# usb-shock-buzzer.net
KiCad netlist of a schematic drawn in EAGLE
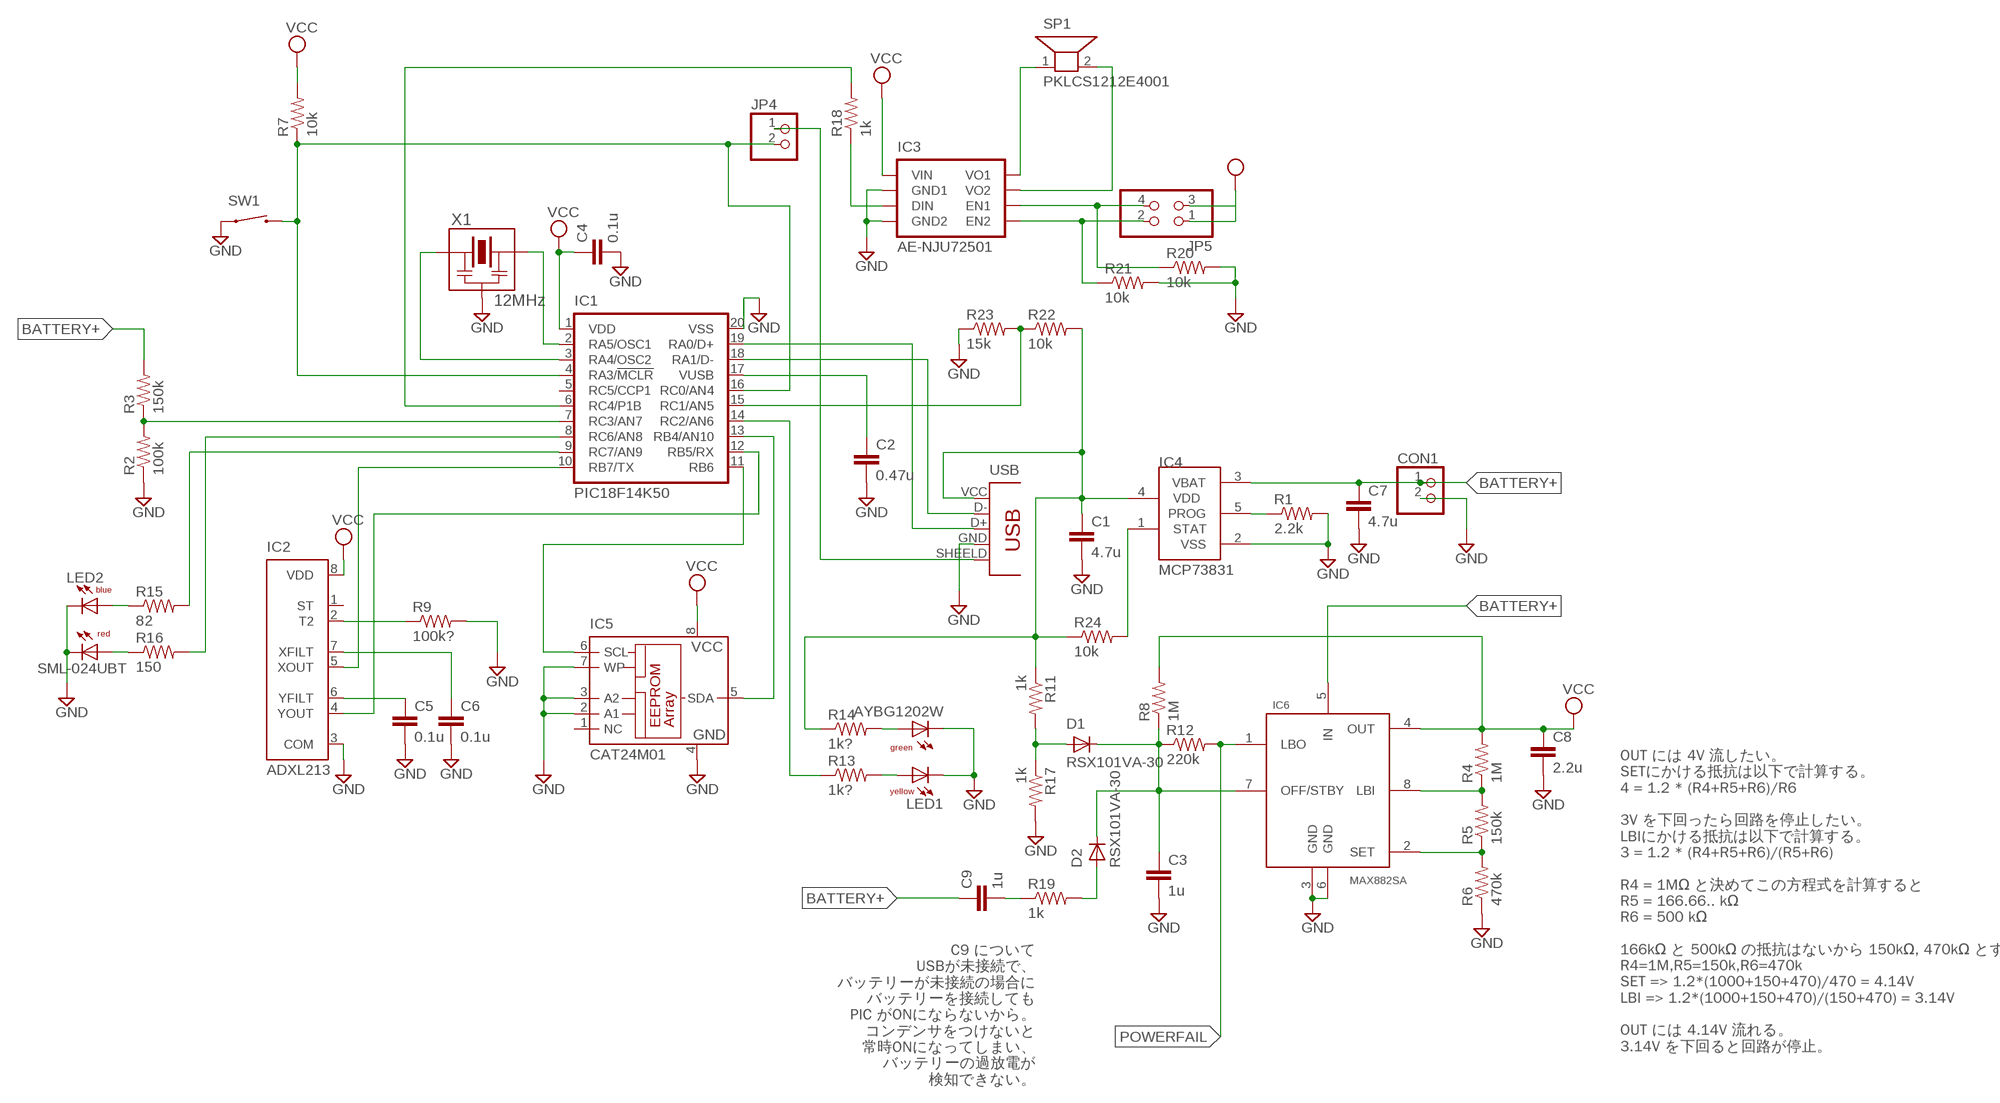
[diagram p0: schematic, sheet 1]

(export (version "E")
  (design (tool "Eeschema 10.0.6"))
  (components
    (comp (ref "C1")
      (value "4.7u")
      (footprint "eagle-import:C0805")
      (libsource (lib "eagle-import") (part "C-EUC0805"))
    )
    (comp (ref "C2")
      (value "0.47u")
      (footprint "eagle-import:C0805")
      (libsource (lib "eagle-import") (part "C-EUC0805"))
    )
    (comp (ref "C3")
      (value "1u")
      (footprint "eagle-import:C0805")
      (libsource (lib "eagle-import") (part "C-EUC0805"))
    )
    (comp (ref "C4")
      (value "0.1u")
      (footprint "eagle-import:C0805")
      (libsource (lib "eagle-import") (part "C-EUC0805"))
    )
    (comp (ref "C5")
      (value "0.1u")
      (footprint "eagle-import:C0805")
      (libsource (lib "eagle-import") (part "C-EUC0805"))
    )
    (comp (ref "C6")
      (value "0.1u")
      (footprint "eagle-import:C0805")
      (libsource (lib "eagle-import") (part "C-EUC0805"))
    )
    (comp (ref "C7")
      (value "4.7u")
      (footprint "eagle-import:C0805")
      (libsource (lib "eagle-import") (part "C-EUC0805"))
    )
    (comp (ref "C8")
      (value "2.2u")
      (footprint "eagle-import:C1206")
      (libsource (lib "eagle-import") (part "C-EUC1206"))
    )
    (comp (ref "C9")
      (value "1u")
      (footprint "eagle-import:C0805")
      (libsource (lib "eagle-import") (part "C-EUC0805"))
    )
    (comp (ref "CON1")
      (value "PH-2PIN")
      (footprint "eagle-import:PH-2PIN")
      (libsource (lib "eagle-import") (part "PH-2PIN"))
    )
    (comp (ref "D1")
      (value "RSX101VA-30")
      (footprint "eagle-import:RSX101VA")
      (libsource (lib "eagle-import") (part "RSX101VA-30"))
    )
    (comp (ref "D2")
      (value "RSX101VA-30")
      (footprint "eagle-import:RSX101VA")
      (libsource (lib "eagle-import") (part "RSX101VA-30"))
    )
    (comp (ref "IC1")
      (value "PIC18F14K50")
      (footprint "eagle-import:SO20")
      (libsource (lib "eagle-import") (part "PIC18F14K50"))
    )
    (comp (ref "IC2")
      (value "ADXL213")
      (footprint "eagle-import:LCC8")
      (libsource (lib "eagle-import") (part "ADXL213"))
    )
    (comp (ref "IC3")
      (value "AE-NJU72501")
      (footprint "eagle-import:AE-NJU72501")
      (libsource (lib "eagle-import") (part "AE-NJU72501"))
    )
    (comp (ref "IC4")
      (value "MCP73831")
      (footprint "eagle-import:SOT23-5L")
      (libsource (lib "eagle-import") (part "MCP73831"))
    )
    (comp (ref "IC5")
      (value "CAT24M01")
      (footprint "eagle-import:SOIC")
      (libsource (lib "eagle-import") (part "CAT24M01"))
    )
    (comp (ref "IC6")
      (value "MAX882SA")
      (footprint "eagle-import:8-SO")
      (libsource (lib "eagle-import") (part "MAX882SA"))
    )
    (comp (ref "JP4")
      (value "PINHD-1X2")
      (footprint "eagle-import:1X02")
      (libsource (lib "eagle-import") (part "PINHD-1X2"))
    )
    (comp (ref "JP5")
      (value "PINHD-2X2")
      (footprint "eagle-import:2X02")
      (libsource (lib "eagle-import") (part "PINHD-2X2"))
    )
    (comp (ref "LED1")
      (value "AYBG1202W")
      (footprint "eagle-import:AYBG1202W")
      (libsource (lib "eagle-import") (part "AYBG1202W"))
    )
    (comp (ref "LED2")
      (value "SML-024UBT")
      (footprint "eagle-import:SML-02")
      (libsource (lib "eagle-import") (part "2COLOR-BR"))
    )
    (comp (ref "R1")
      (value "2.2k")
      (footprint "eagle-import:M0805")
      (libsource (lib "eagle-import") (part "R-US_M0805"))
    )
    (comp (ref "R2")
      (value "100k")
      (footprint "eagle-import:M0805")
      (libsource (lib "eagle-import") (part "R-US_M0805"))
    )
    (comp (ref "R3")
      (value "150k")
      (footprint "eagle-import:M0805")
      (libsource (lib "eagle-import") (part "R-US_M0805"))
    )
    (comp (ref "R4")
      (value "1M")
      (footprint "eagle-import:R0805")
      (libsource (lib "eagle-import") (part "R-US_R0805"))
    )
    (comp (ref "R5")
      (value "150k")
      (footprint "eagle-import:M0805")
      (libsource (lib "eagle-import") (part "R-US_M0805"))
    )
    (comp (ref "R6")
      (value "470k")
      (footprint "eagle-import:M0805")
      (libsource (lib "eagle-import") (part "R-US_M0805"))
    )
    (comp (ref "R7")
      (value "10k")
      (footprint "eagle-import:M0805")
      (libsource (lib "eagle-import") (part "R-US_M0805"))
    )
    (comp (ref "R8")
      (value "1M")
      (footprint "eagle-import:M0805")
      (libsource (lib "eagle-import") (part "R-US_M0805"))
    )
    (comp (ref "R9")
      (value "100k?")
      (footprint "eagle-import:M0805")
      (libsource (lib "eagle-import") (part "R-US_M0805"))
    )
    (comp (ref "R11")
      (value "1k")
      (footprint "eagle-import:M0805")
      (libsource (lib "eagle-import") (part "R-US_M0805"))
    )
    (comp (ref "R12")
      (value "220k")
      (footprint "eagle-import:M0805")
      (libsource (lib "eagle-import") (part "R-US_M0805"))
    )
    (comp (ref "R13")
      (value "1k?")
      (footprint "eagle-import:M0805")
      (libsource (lib "eagle-import") (part "R-US_M0805"))
    )
    (comp (ref "R14")
      (value "1k?")
      (footprint "eagle-import:M0805")
      (libsource (lib "eagle-import") (part "R-US_M0805"))
    )
    (comp (ref "R15")
      (value "82")
      (footprint "eagle-import:M0805")
      (libsource (lib "eagle-import") (part "R-US_M0805"))
    )
    (comp (ref "R16")
      (value "150")
      (footprint "eagle-import:M0805")
      (libsource (lib "eagle-import") (part "R-US_M0805"))
    )
    (comp (ref "R17")
      (value "1k")
      (footprint "eagle-import:M0805")
      (libsource (lib "eagle-import") (part "R-US_M0805"))
    )
    (comp (ref "R18")
      (value "1k")
      (footprint "eagle-import:M0805")
      (libsource (lib "eagle-import") (part "R-US_M0805"))
    )
    (comp (ref "R19")
      (value "1k")
      (footprint "eagle-import:M0805")
      (libsource (lib "eagle-import") (part "R-US_M0805"))
    )
    (comp (ref "R20")
      (value "10k")
      (footprint "eagle-import:M0805")
      (libsource (lib "eagle-import") (part "R-US_M0805"))
    )
    (comp (ref "R21")
      (value "10k")
      (footprint "eagle-import:M0805")
      (libsource (lib "eagle-import") (part "R-US_M0805"))
    )
    (comp (ref "R22")
      (value "10k")
      (footprint "eagle-import:M0805")
      (libsource (lib "eagle-import") (part "R-US_M0805"))
    )
    (comp (ref "R23")
      (value "15k")
      (footprint "eagle-import:M0805")
      (libsource (lib "eagle-import") (part "R-US_M0805"))
    )
    (comp (ref "R24")
      (value "10k")
      (footprint "eagle-import:M0805")
      (libsource (lib "eagle-import") (part "R-US_M0805"))
    )
    (comp (ref "SP1")
      (value "PKLCS1212E4001")
      (footprint "eagle-import:PKLCS1212E4001")
      (libsource (lib "eagle-import") (part "PKLCS1212E4001"))
    )
    (comp (ref "SW1")
      (value "TVBP06")
      (footprint "eagle-import:TVBP06")
      (libsource (lib "eagle-import") (part "TVBP06"))
    )
    (comp (ref "USB")
      (value "TYPE-A+SHILED")
      (footprint "eagle-import:TYPE-A")
      (libsource (lib "eagle-import") (part "TYPE-A+SHILED"))
    )
    (comp (ref "X1")
      (value "12MHz")
      (footprint "eagle-import:CSTCE")
      (libsource (lib "eagle-import") (part "CSTCE12M0G15L"))
    )
  )
  (nets
    (net (code "1") (name "BATTERY+") (class "Default")
      (node (ref "C7") (pin "1") (pinfunction "1_1") (pintype "passive"))
      (node (ref "C9") (pin "1") (pinfunction "1_1") (pintype "passive"))
      (node (ref "CON1") (pin "1") (pinfunction "1_1") (pintype "passive"))
      (node (ref "IC4") (pin "3") (pinfunction "VBAT_3") (pintype "bidirectional"))
      (node (ref "IC6") (pin "5") (pinfunction "IN_5") (pintype "power_in"))
      (node (ref "R3") (pin "2") (pinfunction "2_2") (pintype "passive"))
    )
    (net (code "2") (name "GND") (class "Default")
      (node (ref "C1") (pin "2") (pinfunction "2_2") (pintype "passive"))
      (node (ref "C2") (pin "2") (pinfunction "2_2") (pintype "passive"))
      (node (ref "C3") (pin "2") (pinfunction "2_2") (pintype "passive"))
      (node (ref "C4") (pin "2") (pinfunction "2_2") (pintype "passive"))
      (node (ref "C5") (pin "2") (pinfunction "2_2") (pintype "passive"))
      (node (ref "C6") (pin "2") (pinfunction "2_2") (pintype "passive"))
      (node (ref "C7") (pin "2") (pinfunction "2_2") (pintype "passive"))
      (node (ref "C8") (pin "2") (pinfunction "2_2") (pintype "passive"))
      (node (ref "CON1") (pin "2") (pinfunction "2_2") (pintype "passive"))
      (node (ref "IC1") (pin "20") (pinfunction "VSS_20") (pintype "power_in"))
      (node (ref "IC2") (pin "3") (pinfunction "COM_3") (pintype "input"))
      (node (ref "IC3") (pin "2") (pinfunction "GND1_2") (pintype "power_in"))
      (node (ref "IC3") (pin "4") (pinfunction "GND2_4") (pintype "power_in"))
      (node (ref "IC4") (pin "2") (pinfunction "VSS_2") (pintype "bidirectional"))
      (node (ref "IC5") (pin "2") (pinfunction "A1_2") (pintype "input"))
      (node (ref "IC5") (pin "3") (pinfunction "A2_3") (pintype "input"))
      (node (ref "IC5") (pin "4") (pinfunction "GND_4") (pintype "power_in"))
      (node (ref "IC5") (pin "7") (pinfunction "WP_7") (pintype "input"))
      (node (ref "IC6") (pin "3") (pinfunction "GND_3") (pintype "power_in"))
      (node (ref "IC6") (pin "6") (pinfunction "GND_6") (pintype "power_in"))
      (node (ref "LED1") (pin "2") (pinfunction "CC1_2") (pintype "passive"))
      (node (ref "LED1") (pin "4") (pinfunction "CC2_4") (pintype "passive"))
      (node (ref "LED2") (pin "1") (pinfunction "CC1_1") (pintype "passive"))
      (node (ref "LED2") (pin "3") (pinfunction "CC2_3") (pintype "passive"))
      (node (ref "R1") (pin "2") (pinfunction "2_2") (pintype "passive"))
      (node (ref "R17") (pin "2") (pinfunction "2_2") (pintype "passive"))
      (node (ref "R2") (pin "1") (pinfunction "1_1") (pintype "passive"))
      (node (ref "R20") (pin "2") (pinfunction "2_2") (pintype "passive"))
      (node (ref "R21") (pin "2") (pinfunction "2_2") (pintype "passive"))
      (node (ref "R23") (pin "1") (pinfunction "1_1") (pintype "passive"))
      (node (ref "R6") (pin "1") (pinfunction "1_1") (pintype "passive"))
      (node (ref "R9") (pin "2") (pinfunction "2_2") (pintype "passive"))
      (node (ref "SW1") (pin "1") (pinfunction "1_1") (pintype "passive"))
      (node (ref "USB") (pin "GND") (pinfunction "4_GND") (pintype "power_in"))
      (node (ref "X1") (pin "2") (pinfunction "GND_2") (pintype "bidirectional"))
    )
    (net (code "3") (name "Net-(C9-Pad2)") (class "Default")
      (node (ref "C9") (pin "2") (pinfunction "2_2") (pintype "passive"))
      (node (ref "R19") (pin "1") (pinfunction "1_1") (pintype "passive"))
    )
    (net (code "4") (name "Net-(D1-A)") (class "Default")
      (node (ref "D1") (pin "ANODE") (pinfunction "A_ANODE") (pintype "passive"))
      (node (ref "R11") (pin "2") (pinfunction "2_2") (pintype "passive"))
      (node (ref "R17") (pin "1") (pinfunction "1_1") (pintype "passive"))
    )
    (net (code "5") (name "Net-(D1-C)") (class "Default")
      (node (ref "C3") (pin "1") (pinfunction "1_1") (pintype "passive"))
      (node (ref "D1") (pin "CATHODE") (pinfunction "C_CATHODE") (pintype "passive"))
      (node (ref "D2") (pin "CATHODE") (pinfunction "C_CATHODE") (pintype "passive"))
      (node (ref "IC6") (pin "7") (pinfunction "OFF/STBY_7") (pintype "passive"))
      (node (ref "R12") (pin "1") (pinfunction "1_1") (pintype "passive"))
      (node (ref "R8") (pin "1") (pinfunction "1_1") (pintype "passive"))
    )
    (net (code "6") (name "Net-(D2-A)") (class "Default")
      (node (ref "D2") (pin "ANODE") (pinfunction "A_ANODE") (pintype "passive"))
      (node (ref "R19") (pin "2") (pinfunction "2_2") (pintype "passive"))
    )
    (net (code "7") (name "Net-(IC1-RA0{slash}D+)") (class "Default")
      (node (ref "IC1") (pin "19") (pinfunction "RA0/D+_19") (pintype "bidirectional"))
      (node (ref "USB") (pin "D+") (pinfunction "3_D+") (pintype "passive"))
    )
    (net (code "8") (name "Net-(IC1-RA1{slash}D-)") (class "Default")
      (node (ref "IC1") (pin "18") (pinfunction "RA1/D-_18") (pintype "bidirectional"))
      (node (ref "USB") (pin "D-") (pinfunction "2_D-") (pintype "passive"))
    )
    (net (code "9") (name "Net-(IC1-RA3{slash}~{MCLR})") (class "Default")
      (node (ref "IC1") (pin "16") (pinfunction "RC0/AN4_16") (pintype "bidirectional"))
      (node (ref "IC1") (pin "4") (pinfunction "RA3/~{MCLR}_4") (pintype "bidirectional"))
      (node (ref "JP4") (pin "2") (pinfunction "2_2") (pintype "passive"))
      (node (ref "R7") (pin "1") (pinfunction "1_1") (pintype "passive"))
      (node (ref "SW1") (pin "2") (pinfunction "2_2") (pintype "passive"))
    )
    (net (code "10") (name "Net-(IC1-RA4{slash}OSC2)") (class "Default")
      (node (ref "IC1") (pin "3") (pinfunction "RA4/OSC2_3") (pintype "bidirectional"))
      (node (ref "X1") (pin "1") (pinfunction "LFT_1") (pintype "bidirectional"))
    )
    (net (code "11") (name "Net-(IC1-RA5{slash}OSC1)") (class "Default")
      (node (ref "IC1") (pin "2") (pinfunction "RA5/OSC1_2") (pintype "bidirectional"))
      (node (ref "X1") (pin "3") (pinfunction "RIT_3") (pintype "bidirectional"))
    )
    (net (code "12") (name "Net-(IC1-RB4{slash}AN10)") (class "Default")
      (node (ref "IC1") (pin "13") (pinfunction "RB4/AN10_13") (pintype "bidirectional"))
      (node (ref "IC5") (pin "5") (pinfunction "SDA_5") (pintype "bidirectional"))
    )
    (net (code "13") (name "Net-(IC1-RB5{slash}RX)") (class "Default")
      (node (ref "IC1") (pin "12") (pinfunction "RB5/RX_12") (pintype "bidirectional"))
      (node (ref "IC2") (pin "4") (pinfunction "YOUT_4") (pintype "input"))
    )
    (net (code "14") (name "Net-(IC1-RB6)") (class "Default")
      (node (ref "IC1") (pin "11") (pinfunction "RB6_11") (pintype "bidirectional"))
      (node (ref "IC5") (pin "6") (pinfunction "SCL_6") (pintype "input"))
    )
    (net (code "15") (name "Net-(IC1-RB7{slash}TX)") (class "Default")
      (node (ref "IC1") (pin "10") (pinfunction "RB7/TX_10") (pintype "bidirectional"))
      (node (ref "IC2") (pin "5") (pinfunction "XOUT_5") (pintype "input"))
    )
    (net (code "16") (name "Net-(IC1-RC1{slash}AN5)") (class "Default")
      (node (ref "IC1") (pin "15") (pinfunction "RC1/AN5_15") (pintype "bidirectional"))
      (node (ref "R22") (pin "1") (pinfunction "1_1") (pintype "passive"))
      (node (ref "R23") (pin "2") (pinfunction "2_2") (pintype "passive"))
    )
    (net (code "17") (name "Net-(IC1-RC2{slash}AN6)") (class "Default")
      (node (ref "IC1") (pin "14") (pinfunction "RC2/AN6_14") (pintype "bidirectional"))
      (node (ref "R13") (pin "1") (pinfunction "1_1") (pintype "passive"))
    )
    (net (code "18") (name "Net-(IC1-RC3{slash}AN7)") (class "Default")
      (node (ref "IC1") (pin "7") (pinfunction "RC3/AN7_7") (pintype "bidirectional"))
      (node (ref "R2") (pin "2") (pinfunction "2_2") (pintype "passive"))
      (node (ref "R3") (pin "1") (pinfunction "1_1") (pintype "passive"))
    )
    (net (code "19") (name "Net-(IC1-RC4{slash}P1B)") (class "Default")
      (node (ref "IC1") (pin "6") (pinfunction "RC4/P1B_6") (pintype "bidirectional"))
      (node (ref "R18") (pin "2") (pinfunction "2_2") (pintype "passive"))
    )
    (net (code "20") (name "Net-(IC1-RC6{slash}AN8)") (class "Default")
      (node (ref "IC1") (pin "8") (pinfunction "RC6/AN8_8") (pintype "bidirectional"))
      (node (ref "R16") (pin "2") (pinfunction "2_2") (pintype "passive"))
    )
    (net (code "21") (name "Net-(IC1-RC7{slash}AN9)") (class "Default")
      (node (ref "IC1") (pin "9") (pinfunction "RC7/AN9_9") (pintype "bidirectional"))
      (node (ref "R15") (pin "2") (pinfunction "2_2") (pintype "passive"))
    )
    (net (code "22") (name "Net-(IC1-VUSB)") (class "Default")
      (node (ref "C2") (pin "1") (pinfunction "1_1") (pintype "passive"))
      (node (ref "IC1") (pin "17") (pinfunction "VUSB_17") (pintype "bidirectional"))
    )
    (net (code "23") (name "Net-(IC2-T2)") (class "Default")
      (node (ref "IC2") (pin "2") (pinfunction "T2_2") (pintype "input"))
      (node (ref "R9") (pin "1") (pinfunction "1_1") (pintype "passive"))
    )
    (net (code "24") (name "Net-(IC2-XFILT)") (class "Default")
      (node (ref "C6") (pin "1") (pinfunction "1_1") (pintype "passive"))
      (node (ref "IC2") (pin "7") (pinfunction "XFILT_7") (pintype "input"))
    )
    (net (code "25") (name "Net-(IC2-YFILT)") (class "Default")
      (node (ref "C5") (pin "1") (pinfunction "1_1") (pintype "passive"))
      (node (ref "IC2") (pin "6") (pinfunction "YFILT_6") (pintype "input"))
    )
    (net (code "26") (name "Net-(IC3-DIN)") (class "Default")
      (node (ref "IC3") (pin "3") (pinfunction "DIN_3") (pintype "bidirectional"))
      (node (ref "R18") (pin "1") (pinfunction "1_1") (pintype "passive"))
    )
    (net (code "27") (name "Net-(IC3-EN1)") (class "Default")
      (node (ref "IC3") (pin "6") (pinfunction "EN1_6") (pintype "bidirectional"))
      (node (ref "JP5") (pin "4") (pinfunction "4_4") (pintype "passive"))
      (node (ref "R20") (pin "1") (pinfunction "1_1") (pintype "passive"))
    )
    (net (code "28") (name "Net-(IC3-EN2)") (class "Default")
      (node (ref "IC3") (pin "5") (pinfunction "EN2_5") (pintype "power_in"))
      (node (ref "JP5") (pin "2") (pinfunction "2_2") (pintype "passive"))
      (node (ref "R21") (pin "1") (pinfunction "1_1") (pintype "passive"))
    )
    (net (code "29") (name "Net-(IC3-VO1)") (class "Default")
      (node (ref "IC3") (pin "8") (pinfunction "VO1_8") (pintype "bidirectional"))
      (node (ref "SP1") (pin "1") (pinfunction "1_1") (pintype "passive"))
    )
    (net (code "30") (name "Net-(IC3-VO2)") (class "Default")
      (node (ref "IC3") (pin "7") (pinfunction "VO2_7") (pintype "bidirectional"))
      (node (ref "SP1") (pin "2") (pinfunction "2_2") (pintype "passive"))
    )
    (net (code "31") (name "Net-(IC4-PROG)") (class "Default")
      (node (ref "IC4") (pin "5") (pinfunction "PROG_5") (pintype "bidirectional"))
      (node (ref "R1") (pin "1") (pinfunction "1_1") (pintype "passive"))
    )
    (net (code "32") (name "Net-(IC4-STAT)") (class "Default")
      (node (ref "IC4") (pin "1") (pinfunction "STAT_1") (pintype "bidirectional"))
      (node (ref "R24") (pin "2") (pinfunction "2_2") (pintype "passive"))
    )
    (net (code "33") (name "Net-(IC4-VDD)") (class "Default")
      (node (ref "C1") (pin "1") (pinfunction "1_1") (pintype "passive"))
      (node (ref "IC4") (pin "4") (pinfunction "VDD_4") (pintype "bidirectional"))
      (node (ref "R11") (pin "1") (pinfunction "1_1") (pintype "passive"))
      (node (ref "R14") (pin "1") (pinfunction "1_1") (pintype "passive"))
      (node (ref "R22") (pin "2") (pinfunction "2_2") (pintype "passive"))
      (node (ref "R24") (pin "1") (pinfunction "1_1") (pintype "passive"))
      (node (ref "USB") (pin "VCC") (pinfunction "1_VCC") (pintype "power_in"))
    )
    (net (code "34") (name "Net-(IC6-LBI)") (class "Default")
      (node (ref "IC6") (pin "8") (pinfunction "LBI_8") (pintype "passive"))
      (node (ref "R4") (pin "1") (pinfunction "1_1") (pintype "passive"))
      (node (ref "R5") (pin "2") (pinfunction "2_2") (pintype "passive"))
    )
    (net (code "35") (name "Net-(IC6-SET)") (class "Default")
      (node (ref "IC6") (pin "2") (pinfunction "SET_2") (pintype "passive"))
      (node (ref "R5") (pin "1") (pinfunction "1_1") (pintype "passive"))
      (node (ref "R6") (pin "2") (pinfunction "2_2") (pintype "passive"))
    )
    (net (code "36") (name "Net-(LED1-A1)") (class "Default")
      (node (ref "LED1") (pin "1") (pinfunction "A1_1") (pintype "passive"))
      (node (ref "R13") (pin "2") (pinfunction "2_2") (pintype "passive"))
    )
    (net (code "37") (name "Net-(LED1-A2)") (class "Default")
      (node (ref "LED1") (pin "3") (pinfunction "A2_3") (pintype "passive"))
      (node (ref "R14") (pin "2") (pinfunction "2_2") (pintype "passive"))
    )
    (net (code "38") (name "Net-(LED2-AB)") (class "Default")
      (node (ref "LED2") (pin "2") (pinfunction "AB_2") (pintype "passive"))
      (node (ref "R15") (pin "1") (pinfunction "1_1") (pintype "passive"))
    )
    (net (code "39") (name "Net-(LED2-AR)") (class "Default")
      (node (ref "LED2") (pin "4") (pinfunction "AR_4") (pintype "passive"))
      (node (ref "R16") (pin "1") (pinfunction "1_1") (pintype "passive"))
    )
    (net (code "40") (name "Net-(USB-5)") (class "Default")
      (node (ref "JP4") (pin "1") (pinfunction "1_1") (pintype "passive"))
      (node (ref "USB") (pin "SHEELD") (pinfunction "5_SHEELD") (pintype "passive"))
    )
    (net (code "41") (name "POWERFAIL") (class "Default")
      (node (ref "IC6") (pin "1") (pinfunction "LBO_1") (pintype "open_collector"))
      (node (ref "R12") (pin "2") (pinfunction "2_2") (pintype "passive"))
    )
    (net (code "42") (name "VCC") (class "Default")
      (node (ref "C4") (pin "1") (pinfunction "1_1") (pintype "passive"))
      (node (ref "C8") (pin "1") (pinfunction "1_1") (pintype "passive"))
      (node (ref "IC1") (pin "1") (pinfunction "VDD_1") (pintype "power_in"))
      (node (ref "IC2") (pin "8") (pinfunction "VDD_8") (pintype "input"))
      (node (ref "IC3") (pin "1") (pinfunction "VIN_1") (pintype "power_in"))
      (node (ref "IC5") (pin "8") (pinfunction "VCC_8") (pintype "power_in"))
      (node (ref "IC6") (pin "4") (pinfunction "OUT_4") (pintype "power_in"))
      (node (ref "JP5") (pin "1") (pinfunction "1_1") (pintype "passive"))
      (node (ref "JP5") (pin "3") (pinfunction "3_3") (pintype "passive"))
      (node (ref "R4") (pin "2") (pinfunction "2_2") (pintype "passive"))
      (node (ref "R7") (pin "2") (pinfunction "2_2") (pintype "passive"))
      (node (ref "R8") (pin "2") (pinfunction "2_2") (pintype "passive"))
    )
    (net (code "43") (name "unconnected-(IC1-RC5{slash}CCP1-Pad5)") (class "Default")
      (node (ref "IC1") (pin "5") (pinfunction "RC5/CCP1_5") (pintype "bidirectional"))
    )
    (net (code "44") (name "unconnected-(IC2-ST-Pad1)") (class "Default")
      (node (ref "IC2") (pin "1") (pinfunction "ST_1") (pintype "input"))
    )
    (net (code "45") (name "unconnected-(IC5-NC-Pad1)") (class "Default")
      (node (ref "IC5") (pin "1") (pinfunction "NC_1") (pintype "input"))
    )
  )
)
